# Motorsports_BSPD_EV.net
KiCad netlist of a schematic drawn in Altium Designer
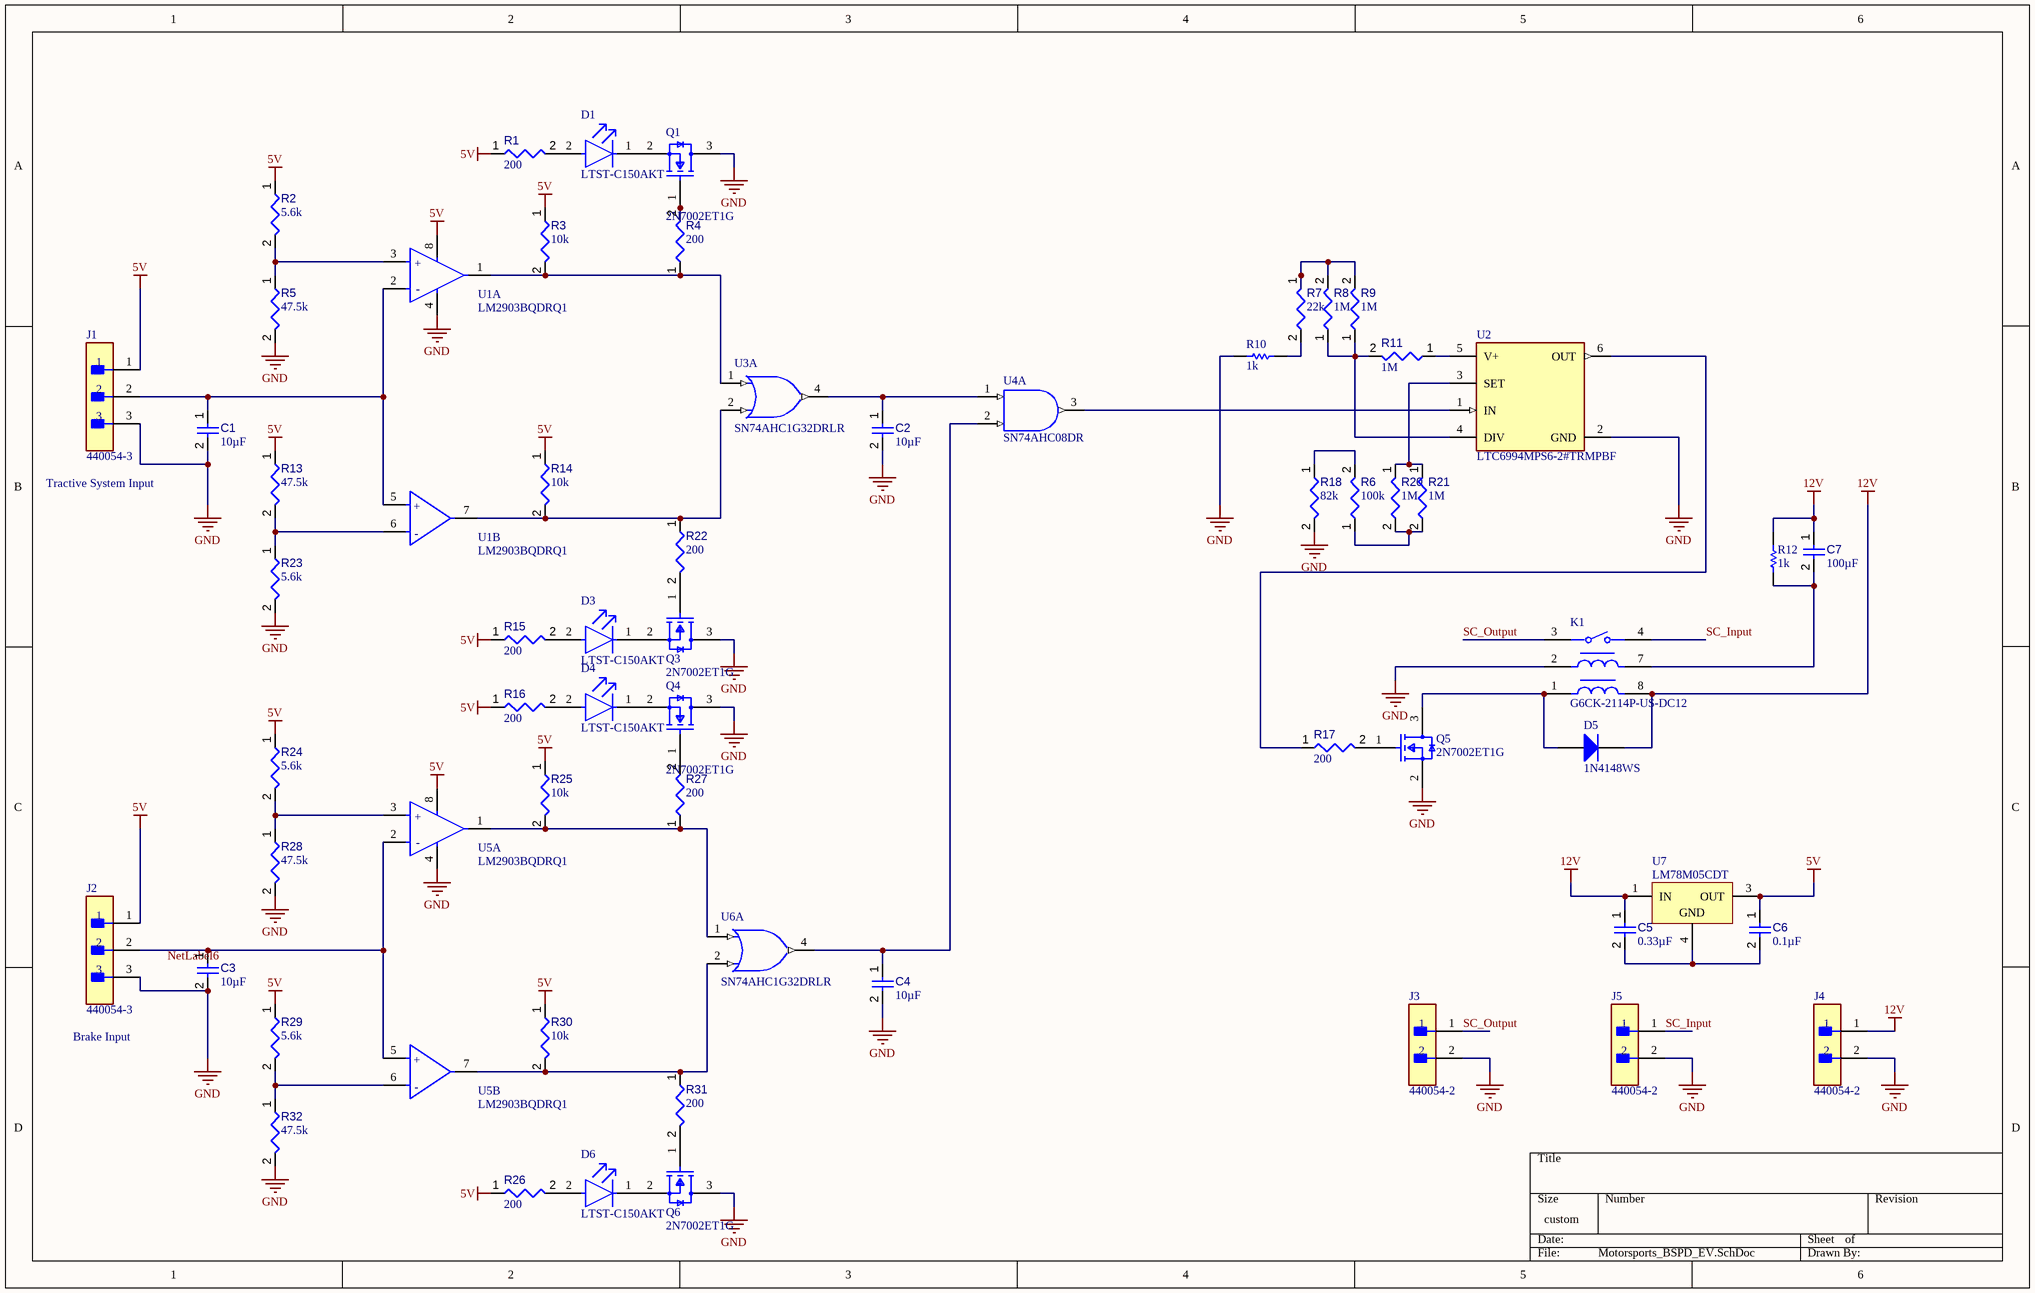
[diagram p0: Motorsports_BSPD_EV.SchDoc]

(export (version "E")
  (design (tool "Eeschema 10.0.6"))
  (components
    (comp (ref "C1")
      (value "10µF")
      (footprint "CAPC0603(1608)100_L")
      (description "Chip Capacitor, 10µF +/-20%, 10V, 0603, Thickness 1 mm")
      (fields (field (name "TOLERANCE") "10%") (field (name "Comment") "Capacitor 10µF +/-20% 10V 0603"))
      (libsource (lib "UGA Motorsports FSAE EV 2026 BSPD") (part "CAP-NP-2"))
    )
    (comp (ref "C2")
      (value "10µF")
      (footprint "CAPC0603(1608)100_L")
      (description "Chip Capacitor, 10µF +/-20%, 10V, 0603, Thickness 1 mm")
      (fields (field (name "TOLERANCE") "10%") (field (name "Comment") "Capacitor 10µF +/-20% 10V 0603"))
      (libsource (lib "UGA Motorsports FSAE EV 2026 BSPD") (part "CAP-NP-2"))
    )
    (comp (ref "C3")
      (value "10µF")
      (footprint "CAPC0603(1608)100_L")
      (description "Chip Capacitor, 10µF +/-20%, 10V, 0603, Thickness 1 mm")
      (fields (field (name "TOLERANCE") "10%") (field (name "Comment") "Capacitor 10µF +/-20% 10V 0603"))
      (libsource (lib "UGA Motorsports FSAE EV 2026 BSPD") (part "CAP-NP-2"))
    )
    (comp (ref "C4")
      (value "10µF")
      (footprint "CAPC0603(1608)100_L")
      (description "Chip Capacitor, 10µF +/-20%, 10V, 0603, Thickness 1 mm")
      (fields (field (name "TOLERANCE") "10%") (field (name "Comment") "Capacitor 10µF +/-20% 10V 0603"))
      (libsource (lib "UGA Motorsports FSAE EV 2026 BSPD") (part "CAP-NP-2"))
    )
    (comp (ref "C5")
      (value "0.33µF")
      (footprint "CAPC0603(1608)100_L")
      (description "Chip Capacitor, 10µF +/-20%, 10V, 0603, Thickness 1 mm")
      (fields (field (name "TOLERANCE") "10%") (field (name "Comment") "Capacitor 10µF +/-20% 10V 0603"))
      (libsource (lib "UGA Motorsports FSAE EV 2026 BSPD") (part "CAP-NP-2"))
    )
    (comp (ref "C6")
      (value "0.1µF")
      (footprint "CAPC0603(1608)100_L")
      (description "Chip Capacitor, 10µF +/-20%, 10V, 0603, Thickness 1 mm")
      (fields (field (name "TOLERANCE") "10%") (field (name "Comment") "Capacitor 10µF +/-20% 10V 0603"))
      (libsource (lib "UGA Motorsports FSAE EV 2026 BSPD") (part "CAP-NP-2"))
    )
    (comp (ref "C7")
      (value "100µF")
      (footprint "CAPC0805(2012)145_L")
      (description "Chip Capacitor, 100µF +/-20%, 6.3V, 0805, Thickness 1.45 mm")
      (fields (field (name "TOLERANCE") "10%") (field (name "Comment") "Capacitor 100µF +/-20% 6.3V 0805"))
      (libsource (lib "UGA Motorsports FSAE EV 2026 BSPD") (part "CAP-NP-2"))
    )
    (comp (ref "D1")
      (value "LTST-C150AKT")
      (footprint "FP-LTST-C150AKT-MFG")
      (description "LED AMBER CLEAR SMD")
      (fields
        (field (name "MANUFACTURER") "Lite-On")
        (field (name "OCTOPART") "https://octopart.com/ltst-c150akt-lite-on-549804")
      )
      (libsource (lib "Altium Content Vault") (part "8706943c75ba83719d021d2fdc84c58"))
    )
    (comp (ref "D3")
      (value "LTST-C150AKT")
      (footprint "FP-LTST-C150AKT-MFG")
      (description "LED AMBER CLEAR SMD")
      (fields
        (field (name "MANUFACTURER") "Lite-On")
        (field (name "OCTOPART") "https://octopart.com/ltst-c150akt-lite-on-549804")
      )
      (libsource (lib "Altium Content Vault") (part "8706943c75ba83719d021d2fdc84c58"))
    )
    (comp (ref "D4")
      (value "LTST-C150AKT")
      (footprint "FP-LTST-C150AKT-MFG")
      (description "LED AMBER CLEAR SMD")
      (fields
        (field (name "MANUFACTURER") "Lite-On")
        (field (name "OCTOPART") "https://octopart.com/ltst-c150akt-lite-on-549804")
      )
      (libsource (lib "Altium Content Vault") (part "8706943c75ba83719d021d2fdc84c58"))
    )
    (comp (ref "D5")
      (value "1N4148WS")
      (footprint "FAIR-SOD-323_V")
      (description "Small Signal Diode, 75 V, 0.15 A, -55 to 150 degC, 2-Pin SOD-323, RoHS, Tape and Reel")
      (fields (field (name "MANUFACTURER") "Fairchild"))
      (libsource (lib "UGA Motorsports FSAE EV 2026 BSPD") (part "D-AK-2"))
    )
    (comp (ref "D6")
      (value "LTST-C150AKT")
      (footprint "FP-LTST-C150AKT-MFG")
      (description "LED AMBER CLEAR SMD")
      (fields
        (field (name "MANUFACTURER") "Lite-On")
        (field (name "OCTOPART") "https://octopart.com/ltst-c150akt-lite-on-549804")
      )
      (libsource (lib "Altium Content Vault") (part "8706943c75ba83719d021d2fdc84c58"))
    )
    (comp (ref "J1")
      (value "440054-3")
      (footprint "FP-440054-3-MFG")
      (description "CONN HEADER VERT 3POS 2MM")
      (fields
        (field (name "OCTOPART") "https://octopart.com/440054-3-te+connectivity-40394845")
        (field (name "MANUFACTURER") "TE Connectivity")
      )
      (libsource (lib "Altium Content Vault") (part "0d3f023dd272f625e17a2be33dea85f"))
    )
    (comp (ref "J2")
      (value "440054-3")
      (footprint "FP-440054-3-MFG")
      (description "CONN HEADER VERT 3POS 2MM")
      (fields
        (field (name "OCTOPART") "https://octopart.com/440054-3-te+connectivity-40394845")
        (field (name "MANUFACTURER") "TE Connectivity")
      )
      (libsource (lib "Altium Content Vault") (part "0d3f023dd272f625e17a2be33dea85f"))
    )
    (comp (ref "J3")
      (value "440054-2")
      (footprint "FP-440054-2-MFG")
      (description "CONN HEADER VERT 2POS 2MM")
      (fields
        (field (name "MANUFACTURER") "TE Connectivity")
        (field (name "OCTOPART") "https://octopart.com/440054-2-te+connectivity-40237927")
      )
      (libsource (lib "Altium Content Vault") (part "3bc925449376181038e59eaffc5286c"))
    )
    (comp (ref "J4")
      (value "440054-2")
      (footprint "FP-440054-2-MFG")
      (description "CONN HEADER VERT 2POS 2MM")
      (fields
        (field (name "MANUFACTURER") "TE Connectivity")
        (field (name "OCTOPART") "https://octopart.com/440054-2-te+connectivity-40237927")
      )
      (libsource (lib "Altium Content Vault") (part "3bc925449376181038e59eaffc5286c"))
    )
    (comp (ref "J5")
      (value "440054-2")
      (footprint "FP-440054-2-MFG")
      (description "CONN HEADER VERT 2POS 2MM")
      (fields
        (field (name "MANUFACTURER") "TE Connectivity")
        (field (name "OCTOPART") "https://octopart.com/440054-2-te+connectivity-40237927")
      )
      (libsource (lib "Altium Content Vault") (part "3bc925449376181038e59eaffc5286c"))
    )
    (comp (ref "K1")
      (value "G6CK-2114P-US-DC12")
      (footprint "FP-G6CK-2114P-US-DC12-MFG")
      (description "RELAY GEN PURPOSE DPST 8A 12V")
      (libsource (lib "Altium Content Vault") (part "248ae269d6825124cdad10c271eae38"))
    )
    (comp (ref "Q1")
      (value "2N7002ET1G")
      (footprint "FP-318-08-IPC_A")
      (description "MOSFET N-CH 60V 260MA SOT-23")
      (libsource (lib "Altium Content Vault") (part "a04dfd38ebfed9f67ad7f4c51a87371"))
    )
    (comp (ref "Q3")
      (value "2N7002ET1G")
      (footprint "FP-318-08-IPC_A")
      (description "MOSFET N-CH 60V 260MA SOT-23")
      (libsource (lib "Altium Content Vault") (part "a04dfd38ebfed9f67ad7f4c51a87371"))
    )
    (comp (ref "Q4")
      (value "2N7002ET1G")
      (footprint "FP-318-08-IPC_A")
      (description "MOSFET N-CH 60V 260MA SOT-23")
      (libsource (lib "Altium Content Vault") (part "a04dfd38ebfed9f67ad7f4c51a87371"))
    )
    (comp (ref "Q5")
      (value "2N7002ET1G")
      (footprint "FP-318-08-IPC_A")
      (description "MOSFET N-CH 60V 260MA SOT-23")
      (libsource (lib "Altium Content Vault") (part "a04dfd38ebfed9f67ad7f4c51a87371"))
    )
    (comp (ref "Q6")
      (value "2N7002ET1G")
      (footprint "FP-318-08-IPC_A")
      (description "MOSFET N-CH 60V 260MA SOT-23")
      (libsource (lib "Altium Content Vault") (part "a04dfd38ebfed9f67ad7f4c51a87371"))
    )
    (comp (ref "R1")
      (value "200")
      (footprint "RESC0402(1005)_L")
      (description "Chip Resistor, 200 Ohms, +/-5 %, 63 mW, -55 to 155 degC, 0402")
      (fields (field (name "POWER") "63mW") (field (name "TOLERANCE") "5%"))
      (libsource (lib "UGA Motorsports FSAE EV 2026 BSPD") (part "RES-2"))
    )
    (comp (ref "R2")
      (value "5.6k")
      (footprint "RESC0402(1005)_L")
      (description "Chip Resistor, 5,6 kOhms, +/-5 %, 63 mW, -55 to 155 degC, 0402")
      (fields (field (name "POWER") "63mW") (field (name "TOLERANCE") "5%"))
      (libsource (lib "UGA Motorsports FSAE EV 2026 BSPD") (part "RES-2"))
    )
    (comp (ref "R3")
      (value "10k")
      (footprint "RESC3216X60X45ML15T20")
      (description "Chip Resistor, 10 KOhm, +/- 1%, 0.25 W, -55 to 155 degC, 1206 (3216 Metric)")
      (fields (field (name "TOLERANCE") "1%") (field (name "POWER") "250mW"))
      (libsource (lib "UGA Motorsports FSAE EV 2026 BSPD") (part "RES-2"))
    )
    (comp (ref "R4")
      (value "200")
      (footprint "RESC0402(1005)_L")
      (description "Chip Resistor, 200 Ohms, +/-5 %, 63 mW, -55 to 155 degC, 0402")
      (fields (field (name "POWER") "63mW") (field (name "TOLERANCE") "5%"))
      (libsource (lib "UGA Motorsports FSAE EV 2026 BSPD") (part "RES-2"))
    )
    (comp (ref "R5")
      (value "47.5k")
      (footprint "RESC0402(1005)_L")
      (description "Chip Resistor, 47,5 kOhms, +/-1 %, 63 mW, -55 to 155 degC, 0402")
      (fields (field (name "POWER") "63mW") (field (name "TOLERANCE") "1%"))
      (libsource (lib "UGA Motorsports FSAE EV 2026 BSPD") (part "RES-2"))
    )
    (comp (ref "R6")
      (value "100k")
      (footprint "RESC1005X40X25ML05T05")
      (description "Chip Resistor, 100 KOhm, +/- 1%, 0.1 W, -55 to 155 degC, 0402 (1005 Metric)")
      (fields (field (name "POWER") "100mW") (field (name "TOLERANCE") "1%"))
      (libsource (lib "UGA Motorsports FSAE EV 2026 BSPD") (part "RES-2"))
    )
    (comp (ref "R7")
      (value "22k")
      (footprint "RESC0402(1005)_L")
      (description "Chip Resistor, 22 kOhms, +/-1 %, 63 mW, -55 to 155 degC, 0402")
      (fields (field (name "POWER") "63mW") (field (name "TOLERANCE") "1%"))
      (libsource (lib "UGA Motorsports FSAE EV 2026 BSPD") (part "RES-2"))
    )
    (comp (ref "R8")
      (value "1M")
      (footprint "RESC0402(1005)_L")
      (description "Chip Resistor, 1 MOhms, +/-5 %, 63 mW, -55 to 155 degC, 0402")
      (fields (field (name "POWER") "63mW") (field (name "TOLERANCE") "5%"))
      (libsource (lib "UGA Motorsports FSAE EV 2026 BSPD") (part "RES-2"))
    )
    (comp (ref "R9")
      (value "1M")
      (footprint "RESC0402(1005)_L")
      (description "Chip Resistor, 1 MOhms, +/-5 %, 63 mW, -55 to 155 degC, 0402")
      (fields (field (name "POWER") "63mW") (field (name "TOLERANCE") "5%"))
      (libsource (lib "UGA Motorsports FSAE EV 2026 BSPD") (part "RES-2"))
    )
    (comp (ref "R10")
      (value "1k")
      (footprint "RESC1005X40X25ML05T05")
      (description "Chip Resistor, 1 KOhm, +/- 1%, 0.1 W, -55 to 155 degC, 0402 (1005 Metric)")
      (fields (field (name "POWER") "100mW") (field (name "TOLERANCE") "1%"))
      (libsource (lib "") (part "RES-2_1"))
    )
    (comp (ref "R11")
      (value "1M")
      (footprint "RESC0402(1005)_L")
      (description "Chip Resistor, 1 MOhms, +/-5 %, 63 mW, -55 to 155 degC, 0402")
      (fields (field (name "POWER") "63mW") (field (name "TOLERANCE") "5%"))
      (libsource (lib "UGA Motorsports FSAE EV 2026 BSPD") (part "RES-2"))
    )
    (comp (ref "R12")
      (value "1k")
      (footprint "RESC1005X40X25ML05T05")
      (description "Chip Resistor, 1 KOhm, +/- 1%, 0.1 W, -55 to 155 degC, 0402 (1005 Metric)")
      (fields (field (name "POWER") "100mW") (field (name "TOLERANCE") "1%"))
      (libsource (lib "") (part "RES-2_1"))
    )
    (comp (ref "R13")
      (value "47.5k")
      (footprint "RESC0402(1005)_L")
      (description "Chip Resistor, 47,5 kOhms, +/-1 %, 63 mW, -55 to 155 degC, 0402")
      (fields (field (name "POWER") "63mW") (field (name "TOLERANCE") "1%"))
      (libsource (lib "UGA Motorsports FSAE EV 2026 BSPD") (part "RES-2"))
    )
    (comp (ref "R14")
      (value "10k")
      (footprint "RESC3216X60X45ML15T20")
      (description "Chip Resistor, 10 KOhm, +/- 1%, 0.25 W, -55 to 155 degC, 1206 (3216 Metric)")
      (fields (field (name "TOLERANCE") "1%") (field (name "POWER") "250mW"))
      (libsource (lib "UGA Motorsports FSAE EV 2026 BSPD") (part "RES-2"))
    )
    (comp (ref "R15")
      (value "200")
      (footprint "RESC0402(1005)_L")
      (description "Chip Resistor, 200 Ohms, +/-5 %, 63 mW, -55 to 155 degC, 0402")
      (fields (field (name "POWER") "63mW") (field (name "TOLERANCE") "5%"))
      (libsource (lib "UGA Motorsports FSAE EV 2026 BSPD") (part "RES-2"))
    )
    (comp (ref "R16")
      (value "200")
      (footprint "RESC0402(1005)_L")
      (description "Chip Resistor, 200 Ohms, +/-5 %, 63 mW, -55 to 155 degC, 0402")
      (fields (field (name "POWER") "63mW") (field (name "TOLERANCE") "5%"))
      (libsource (lib "UGA Motorsports FSAE EV 2026 BSPD") (part "RES-2"))
    )
    (comp (ref "R17")
      (value "200")
      (footprint "RESC0402(1005)_L")
      (description "Chip Resistor, 200 Ohms, +/-5 %, 63 mW, -55 to 155 degC, 0402")
      (fields (field (name "POWER") "63mW") (field (name "TOLERANCE") "5%"))
      (libsource (lib "UGA Motorsports FSAE EV 2026 BSPD") (part "RES-2"))
    )
    (comp (ref "R18")
      (value "82k")
      (footprint "RESC0402(1005)_L")
      (description "Chip Resistor, 82 kOhms, +/-1 %, 63 mW, -55 to 155 degC, 0402")
      (fields (field (name "POWER") "63mW") (field (name "TOLERANCE") "1%"))
      (libsource (lib "UGA Motorsports FSAE EV 2026 BSPD") (part "RES-2"))
    )
    (comp (ref "R20")
      (value "1M")
      (footprint "RESC0402(1005)_L")
      (description "Chip Resistor, 1 MOhms, +/-5 %, 63 mW, -55 to 155 degC, 0402")
      (fields (field (name "POWER") "63mW") (field (name "TOLERANCE") "5%"))
      (libsource (lib "UGA Motorsports FSAE EV 2026 BSPD") (part "RES-2"))
    )
    (comp (ref "R21")
      (value "1M")
      (footprint "RESC0402(1005)_L")
      (description "Chip Resistor, 1 MOhms, +/-5 %, 63 mW, -55 to 155 degC, 0402")
      (fields (field (name "POWER") "63mW") (field (name "TOLERANCE") "5%"))
      (libsource (lib "UGA Motorsports FSAE EV 2026 BSPD") (part "RES-2"))
    )
    (comp (ref "R22")
      (value "200")
      (footprint "RESC0402(1005)_L")
      (description "Chip Resistor, 200 Ohms, +/-5 %, 63 mW, -55 to 155 degC, 0402")
      (fields (field (name "POWER") "63mW") (field (name "TOLERANCE") "5%"))
      (libsource (lib "UGA Motorsports FSAE EV 2026 BSPD") (part "RES-2"))
    )
    (comp (ref "R23")
      (value "5.6k")
      (footprint "RESC0402(1005)_L")
      (description "Chip Resistor, 5,6 kOhms, +/-5 %, 63 mW, -55 to 155 degC, 0402")
      (fields (field (name "POWER") "63mW") (field (name "TOLERANCE") "5%"))
      (libsource (lib "UGA Motorsports FSAE EV 2026 BSPD") (part "RES-2"))
    )
    (comp (ref "R24")
      (value "5.6k")
      (footprint "RESC0402(1005)_L")
      (description "Chip Resistor, 5,6 kOhms, +/-5 %, 63 mW, -55 to 155 degC, 0402")
      (fields (field (name "POWER") "63mW") (field (name "TOLERANCE") "5%"))
      (libsource (lib "UGA Motorsports FSAE EV 2026 BSPD") (part "RES-2"))
    )
    (comp (ref "R25")
      (value "10k")
      (footprint "RESC3216X60X45ML15T20")
      (description "Chip Resistor, 10 KOhm, +/- 1%, 0.25 W, -55 to 155 degC, 1206 (3216 Metric)")
      (fields (field (name "TOLERANCE") "1%") (field (name "POWER") "250mW"))
      (libsource (lib "UGA Motorsports FSAE EV 2026 BSPD") (part "RES-2"))
    )
    (comp (ref "R26")
      (value "200")
      (footprint "RESC0402(1005)_L")
      (description "Chip Resistor, 200 Ohms, +/-5 %, 63 mW, -55 to 155 degC, 0402")
      (fields (field (name "POWER") "63mW") (field (name "TOLERANCE") "5%"))
      (libsource (lib "UGA Motorsports FSAE EV 2026 BSPD") (part "RES-2"))
    )
    (comp (ref "R27")
      (value "200")
      (footprint "RESC0402(1005)_L")
      (description "Chip Resistor, 200 Ohms, +/-5 %, 63 mW, -55 to 155 degC, 0402")
      (fields (field (name "POWER") "63mW") (field (name "TOLERANCE") "5%"))
      (libsource (lib "UGA Motorsports FSAE EV 2026 BSPD") (part "RES-2"))
    )
    (comp (ref "R28")
      (value "47.5k")
      (footprint "RESC0402(1005)_L")
      (description "Chip Resistor, 47,5 kOhms, +/-1 %, 63 mW, -55 to 155 degC, 0402")
      (fields (field (name "POWER") "63mW") (field (name "TOLERANCE") "1%"))
      (libsource (lib "UGA Motorsports FSAE EV 2026 BSPD") (part "RES-2"))
    )
    (comp (ref "R29")
      (value "5.6k")
      (footprint "RESC0402(1005)_L")
      (description "Chip Resistor, 5,6 kOhms, +/-5 %, 63 mW, -55 to 155 degC, 0402")
      (fields (field (name "POWER") "63mW") (field (name "TOLERANCE") "5%"))
      (libsource (lib "UGA Motorsports FSAE EV 2026 BSPD") (part "RES-2"))
    )
    (comp (ref "R30")
      (value "10k")
      (footprint "RESC3216X60X45ML15T20")
      (description "Chip Resistor, 10 KOhm, +/- 1%, 0.25 W, -55 to 155 degC, 1206 (3216 Metric)")
      (fields (field (name "TOLERANCE") "1%") (field (name "POWER") "250mW"))
      (libsource (lib "UGA Motorsports FSAE EV 2026 BSPD") (part "RES-2"))
    )
    (comp (ref "R31")
      (value "200")
      (footprint "RESC0402(1005)_L")
      (description "Chip Resistor, 200 Ohms, +/-5 %, 63 mW, -55 to 155 degC, 0402")
      (fields (field (name "POWER") "63mW") (field (name "TOLERANCE") "5%"))
      (libsource (lib "UGA Motorsports FSAE EV 2026 BSPD") (part "RES-2"))
    )
    (comp (ref "R32")
      (value "47.5k")
      (footprint "RESC0402(1005)_L")
      (description "Chip Resistor, 47,5 kOhms, +/-1 %, 63 mW, -55 to 155 degC, 0402")
      (fields (field (name "POWER") "63mW") (field (name "TOLERANCE") "1%"))
      (libsource (lib "UGA Motorsports FSAE EV 2026 BSPD") (part "RES-2"))
    )
    (comp (ref "U1")
      (value "LM2903BQDRQ1")
      (footprint "FP-D0008A-MFG")
      (description "Automotive Dual Comparators")
      (fields
        (field (name "MANUFACTURER") "Texas Instruments")
        (field (name "OCTOPART") "https://octopart.com/lm2903bqdrq1-texas+instruments-107383907")
      )
      (libsource (lib "Altium Content Vault") (part "d0dfe35d032f86ae96c0c3919f86c94"))
    )
    (comp (ref "U2")
      (value "LTC6994MPS6-2#TRMPBF")
      (footprint "FP-S6-6-05-08-1636-MFG")
      (description "IC DELAY LINE 8TAP PROG TSOT23-6")
      (libsource (lib "Altium Content Vault") (part "5813ba12ddd9e7c0a16514c8272ed63"))
    )
    (comp (ref "U3")
      (value "SN74AHC1G32DRLR")
      (footprint "DRL0005A_N")
      (description "Single 2-Input Positive-OR Gate, DRL0005A, LARGE T&R")
      (fields
        (field (name "GENERIC PART NUMBER") "SN74AHC1G32")
        (field (name "MANUFACTURER") "Texas Instruments")
      )
      (libsource (lib "Altium Content Vault") (part "TI-SN74XXX1X32-5"))
    )
    (comp (ref "U4")
      (value "SN74AHC08DR")
      (footprint "D0014A_L")
      (description "Quadruple 2-Input Positive-AND Gates, D0014A, LARGE T&R")
      (fields
        (field (name "GENERIC PART NUMBER") "SN74AHC08")
        (field (name "MANUFACTURER") "Texas Instruments")
      )
      (libsource (lib "Altium Content Vault") (part "TI-AND-4-2IN-14"))
    )
    (comp (ref "U5")
      (value "LM2903BQDRQ1")
      (footprint "FP-D0008A-MFG")
      (description "Automotive Dual Comparators")
      (fields
        (field (name "MANUFACTURER") "Texas Instruments")
        (field (name "OCTOPART") "https://octopart.com/lm2903bqdrq1-texas+instruments-107383907")
      )
      (libsource (lib "Altium Content Vault") (part "d0dfe35d032f86ae96c0c3919f86c94"))
    )
    (comp (ref "U6")
      (value "SN74AHC1G32DRLR")
      (footprint "DRL0005A_N")
      (description "Single 2-Input Positive-OR Gate, DRL0005A, LARGE T&R")
      (fields
        (field (name "GENERIC PART NUMBER") "SN74AHC1G32")
        (field (name "MANUFACTURER") "Texas Instruments")
      )
      (libsource (lib "Altium Content Vault") (part "TI-SN74XXX1X32-5"))
    )
    (comp (ref "U7")
      (value "LM78M05CDT")
      (footprint "NDP0003B_N")
      (description "3-Terminal Positive Voltage Regulators, 3-pin TO-252")
      (fields (field (name "MANUFACTURER") "Texas Instruments"))
      (libsource (lib "Altium Content Vault") (part "PM-REG-LM78M05-SOT3"))
    )
  )
  (nets
    (net (code "2") (name "/SC_Input") (class "Default")
      (node (ref "J5") (pin "1") (pinfunction "1_1") (pintype "passive"))
      (node (ref "K1") (pin "4") (pinfunction "4_4") (pintype "passive"))
    )
    (net (code "3") (name "/SC_Output") (class "Default")
      (node (ref "J3") (pin "1") (pinfunction "1_1") (pintype "passive"))
      (node (ref "K1") (pin "3") (pinfunction "3_3") (pintype "passive"))
    )
    (net (code "4") (name "5V") (class "Default")
      (node (ref "C6") (pin "1") (pinfunction "1_1") (pintype "passive"))
      (node (ref "J1") (pin "1") (pinfunction "1_1") (pintype "passive"))
      (node (ref "J2") (pin "1") (pinfunction "1_1") (pintype "passive"))
      (node (ref "R1") (pin "1") (pinfunction "1_1") (pintype "passive"))
      (node (ref "R13") (pin "1") (pinfunction "1_1") (pintype "passive"))
      (node (ref "R14") (pin "1") (pinfunction "1_1") (pintype "passive"))
      (node (ref "R15") (pin "1") (pinfunction "1_1") (pintype "passive"))
      (node (ref "R16") (pin "1") (pinfunction "1_1") (pintype "passive"))
      (node (ref "R2") (pin "1") (pinfunction "1_1") (pintype "passive"))
      (node (ref "R24") (pin "1") (pinfunction "1_1") (pintype "passive"))
      (node (ref "R25") (pin "1") (pinfunction "1_1") (pintype "passive"))
      (node (ref "R26") (pin "1") (pinfunction "1_1") (pintype "passive"))
      (node (ref "R29") (pin "1") (pinfunction "1_1") (pintype "passive"))
      (node (ref "R3") (pin "1") (pinfunction "1_1") (pintype "passive"))
      (node (ref "R30") (pin "1") (pinfunction "1_1") (pintype "passive"))
      (node (ref "U1") (pin "8") (pinfunction "VCC_8") (pintype "power_in"))
      (node (ref "U5") (pin "8") (pinfunction "VCC_8") (pintype "power_in"))
      (node (ref "U7") (pin "3") (pinfunction "OUT_3") (pintype "power_in"))
    )
    (net (code "5") (name "12V") (class "Default")
      (node (ref "C5") (pin "1") (pinfunction "1_1") (pintype "passive"))
      (node (ref "C7") (pin "1") (pinfunction "1_1") (pintype "passive"))
      (node (ref "D5") (pin "2") (pinfunction "K_2") (pintype "passive"))
      (node (ref "J4") (pin "1") (pinfunction "1_1") (pintype "passive"))
      (node (ref "K1") (pin "8") (pinfunction "S+_8") (pintype "passive"))
      (node (ref "R12") (pin "2") (pinfunction "2_2") (pintype "passive"))
      (node (ref "U7") (pin "1") (pinfunction "IN_1") (pintype "power_in"))
    )
    (net (code "6") (name "GND") (class "Default")
      (node (ref "C1") (pin "2") (pinfunction "2_2") (pintype "passive"))
      (node (ref "C2") (pin "2") (pinfunction "2_2") (pintype "passive"))
      (node (ref "C3") (pin "2") (pinfunction "2_2") (pintype "passive"))
      (node (ref "C4") (pin "2") (pinfunction "2_2") (pintype "passive"))
      (node (ref "J1") (pin "3") (pinfunction "3_3") (pintype "passive"))
      (node (ref "J2") (pin "3") (pinfunction "3_3") (pintype "passive"))
      (node (ref "J3") (pin "2") (pinfunction "2_2") (pintype "passive"))
      (node (ref "J4") (pin "2") (pinfunction "2_2") (pintype "passive"))
      (node (ref "J5") (pin "2") (pinfunction "2_2") (pintype "passive"))
      (node (ref "K1") (pin "2") (pinfunction "R-_2") (pintype "passive"))
      (node (ref "Q1") (pin "3") (pinfunction "Drain_3") (pintype "passive"))
      (node (ref "Q3") (pin "3") (pinfunction "Drain_3") (pintype "passive"))
      (node (ref "Q4") (pin "3") (pinfunction "Drain_3") (pintype "passive"))
      (node (ref "Q5") (pin "2") (pinfunction "Source_2") (pintype "passive"))
      (node (ref "Q6") (pin "3") (pinfunction "Drain_3") (pintype "passive"))
      (node (ref "R10") (pin "2") (pinfunction "2_2") (pintype "passive"))
      (node (ref "R18") (pin "2") (pinfunction "2_2") (pintype "passive"))
      (node (ref "R23") (pin "2") (pinfunction "2_2") (pintype "passive"))
      (node (ref "R28") (pin "2") (pinfunction "2_2") (pintype "passive"))
      (node (ref "R32") (pin "2") (pinfunction "2_2") (pintype "passive"))
      (node (ref "R5") (pin "2") (pinfunction "2_2") (pintype "passive"))
      (node (ref "U1") (pin "4") (pinfunction "GND_4") (pintype "power_in"))
      (node (ref "U2") (pin "2") (pinfunction "GND_2") (pintype "power_in"))
      (node (ref "U5") (pin "4") (pinfunction "GND_4") (pintype "power_in"))
    )
    (net (code "7") (name "Net-(D1-A)") (class "Default")
      (node (ref "D1") (pin "2") (pinfunction "A_2") (pintype "passive"))
      (node (ref "R1") (pin "2") (pinfunction "2_2") (pintype "passive"))
    )
    (net (code "8") (name "Net-(D1-C)") (class "Default")
      (node (ref "D1") (pin "1") (pinfunction "C_1") (pintype "passive"))
      (node (ref "Q1") (pin "2") (pinfunction "Source_2") (pintype "passive"))
    )
    (net (code "9") (name "Net-(D3-A)") (class "Default")
      (node (ref "D3") (pin "2") (pinfunction "A_2") (pintype "passive"))
      (node (ref "R15") (pin "2") (pinfunction "2_2") (pintype "passive"))
    )
    (net (code "10") (name "Net-(D3-C)") (class "Default")
      (node (ref "D3") (pin "1") (pinfunction "C_1") (pintype "passive"))
      (node (ref "Q3") (pin "2") (pinfunction "Source_2") (pintype "passive"))
    )
    (net (code "11") (name "Net-(D4-A)") (class "Default")
      (node (ref "D4") (pin "2") (pinfunction "A_2") (pintype "passive"))
      (node (ref "R16") (pin "2") (pinfunction "2_2") (pintype "passive"))
    )
    (net (code "12") (name "Net-(D4-C)") (class "Default")
      (node (ref "D4") (pin "1") (pinfunction "C_1") (pintype "passive"))
      (node (ref "Q4") (pin "2") (pinfunction "Source_2") (pintype "passive"))
    )
    (net (code "13") (name "Net-(D5-A)") (class "Default")
      (node (ref "D5") (pin "1") (pinfunction "A_1") (pintype "passive"))
      (node (ref "K1") (pin "1") (pinfunction "S-_1") (pintype "passive"))
      (node (ref "Q5") (pin "3") (pinfunction "Drain_3") (pintype "passive"))
    )
    (net (code "14") (name "Net-(D6-A)") (class "Default")
      (node (ref "D6") (pin "2") (pinfunction "A_2") (pintype "passive"))
      (node (ref "R26") (pin "2") (pinfunction "2_2") (pintype "passive"))
    )
    (net (code "15") (name "Net-(D6-C)") (class "Default")
      (node (ref "D6") (pin "1") (pinfunction "C_1") (pintype "passive"))
      (node (ref "Q6") (pin "2") (pinfunction "Source_2") (pintype "passive"))
    )
    (net (code "16") (name "Net-(K1-R+)") (class "Default")
      (node (ref "C7") (pin "2") (pinfunction "2_2") (pintype "passive"))
      (node (ref "K1") (pin "7") (pinfunction "R+_7") (pintype "passive"))
      (node (ref "R12") (pin "1") (pinfunction "1_1") (pintype "passive"))
    )
    (net (code "17") (name "Net-(Q1-Gate)") (class "Default")
      (node (ref "Q1") (pin "1") (pinfunction "Gate_1") (pintype "passive"))
      (node (ref "R4") (pin "2") (pinfunction "2_2") (pintype "passive"))
    )
    (net (code "18") (name "Net-(Q3-Gate)") (class "Default")
      (node (ref "Q3") (pin "1") (pinfunction "Gate_1") (pintype "passive"))
      (node (ref "R22") (pin "2") (pinfunction "2_2") (pintype "passive"))
    )
    (net (code "19") (name "Net-(Q4-Gate)") (class "Default")
      (node (ref "Q4") (pin "1") (pinfunction "Gate_1") (pintype "passive"))
      (node (ref "R27") (pin "2") (pinfunction "2_2") (pintype "passive"))
    )
    (net (code "20") (name "Net-(Q5-Gate)") (class "Default")
      (node (ref "Q5") (pin "1") (pinfunction "Gate_1") (pintype "passive"))
      (node (ref "R17") (pin "2") (pinfunction "2_2") (pintype "passive"))
    )
    (net (code "21") (name "Net-(Q6-Gate)") (class "Default")
      (node (ref "Q6") (pin "1") (pinfunction "Gate_1") (pintype "passive"))
      (node (ref "R31") (pin "2") (pinfunction "2_2") (pintype "passive"))
    )
    (net (code "22") (name "Net-(R7-Pad1)") (class "Default")
      (node (ref "R7") (pin "1") (pinfunction "1_1") (pintype "passive"))
      (node (ref "R8") (pin "2") (pinfunction "2_2") (pintype "passive"))
      (node (ref "R9") (pin "2") (pinfunction "2_2") (pintype "passive"))
    )
    (net (code "23") (name "Net-(R10-Pad1)") (class "Default")
      (node (ref "R10") (pin "1") (pinfunction "1_1") (pintype "passive"))
      (node (ref "R7") (pin "2") (pinfunction "2_2") (pintype "passive"))
    )
    (net (code "24") (name "Net-(R18-Pad1)") (class "Default")
      (node (ref "R18") (pin "1") (pinfunction "1_1") (pintype "passive"))
      (node (ref "R6") (pin "2") (pinfunction "2_2") (pintype "passive"))
    )
    (net (code "25") (name "Net-(R20-Pad2)") (class "Default")
      (node (ref "R20") (pin "2") (pinfunction "2_2") (pintype "passive"))
      (node (ref "R21") (pin "2") (pinfunction "2_2") (pintype "passive"))
      (node (ref "R6") (pin "1") (pinfunction "1_1") (pintype "passive"))
    )
    (net (code "26") (name "Net-(U1A-1IN+)") (class "Default")
      (node (ref "R2") (pin "2") (pinfunction "2_2") (pintype "passive"))
      (node (ref "R5") (pin "1") (pinfunction "1_1") (pintype "passive"))
      (node (ref "U1") (pin "3") (pinfunction "1IN+_3") (pintype "tri_state"))
    )
    (net (code "27") (name "Net-(U1A-1IN-)") (class "Default")
      (node (ref "C1") (pin "1") (pinfunction "1_1") (pintype "passive"))
      (node (ref "J1") (pin "2") (pinfunction "2_2") (pintype "passive"))
      (node (ref "U1") (pin "2") (pinfunction "1IN-_2") (pintype "tri_state"))
      (node (ref "U1") (pin "5") (pinfunction "2IN+_5") (pintype "tri_state"))
    )
    (net (code "28") (name "Net-(U1A-1OUT)") (class "Default")
      (node (ref "R3") (pin "2") (pinfunction "2_2") (pintype "passive"))
      (node (ref "R4") (pin "1") (pinfunction "1_1") (pintype "passive"))
      (node (ref "U1") (pin "1") (pinfunction "1OUT_1") (pintype "passive"))
      (node (ref "U3") (pin "1") (pinfunction "A_1") (pintype "input"))
    )
    (net (code "29") (name "Net-(U1B-2IN-)") (class "Default")
      (node (ref "R13") (pin "2") (pinfunction "2_2") (pintype "passive"))
      (node (ref "R23") (pin "1") (pinfunction "1_1") (pintype "passive"))
      (node (ref "U1") (pin "6") (pinfunction "2IN-_6") (pintype "tri_state"))
    )
    (net (code "30") (name "Net-(U1B-2OUT)") (class "Default")
      (node (ref "R14") (pin "2") (pinfunction "2_2") (pintype "passive"))
      (node (ref "R22") (pin "1") (pinfunction "1_1") (pintype "passive"))
      (node (ref "U1") (pin "7") (pinfunction "2OUT_7") (pintype "passive"))
      (node (ref "U3") (pin "2") (pinfunction "B_2") (pintype "input"))
    )
    (net (code "31") (name "Net-(U2-DIV)") (class "Default")
      (node (ref "R11") (pin "2") (pinfunction "2_2") (pintype "passive"))
      (node (ref "R8") (pin "1") (pinfunction "1_1") (pintype "passive"))
      (node (ref "R9") (pin "1") (pinfunction "1_1") (pintype "passive"))
      (node (ref "U2") (pin "4") (pinfunction "DIV_4") (pintype "passive"))
    )
    (net (code "32") (name "Net-(U2-IN)") (class "Default")
      (node (ref "U2") (pin "1") (pinfunction "IN_1") (pintype "input"))
      (node (ref "U4") (pin "3") (pinfunction "1Y_3") (pintype "output"))
    )
    (net (code "33") (name "Net-(U2-OUT)") (class "Default")
      (node (ref "R17") (pin "1") (pinfunction "1_1") (pintype "passive"))
      (node (ref "U2") (pin "6") (pinfunction "OUT_6") (pintype "output"))
    )
    (net (code "34") (name "Net-(U2-SET)") (class "Default")
      (node (ref "R20") (pin "1") (pinfunction "1_1") (pintype "passive"))
      (node (ref "R21") (pin "1") (pinfunction "1_1") (pintype "passive"))
      (node (ref "U2") (pin "3") (pinfunction "SET_3") (pintype "passive"))
    )
    (net (code "35") (name "Net-(U2-V+)") (class "Default")
      (node (ref "R11") (pin "1") (pinfunction "1_1") (pintype "passive"))
      (node (ref "U2") (pin "5") (pinfunction "V+_5") (pintype "power_in"))
    )
    (net (code "36") (name "Net-(U3A-Y)") (class "Default")
      (node (ref "C2") (pin "1") (pinfunction "1_1") (pintype "passive"))
      (node (ref "U3") (pin "4") (pinfunction "Y_4") (pintype "output"))
      (node (ref "U4") (pin "1") (pinfunction "1A_1") (pintype "input"))
    )
    (net (code "37") (name "Net-(U4A-1B)") (class "Default")
      (node (ref "C4") (pin "1") (pinfunction "1_1") (pintype "passive"))
      (node (ref "U4") (pin "2") (pinfunction "1B_2") (pintype "input"))
      (node (ref "U6") (pin "4") (pinfunction "Y_4") (pintype "output"))
    )
    (net (code "38") (name "Net-(U5A-1IN+)") (class "Default")
      (node (ref "R24") (pin "2") (pinfunction "2_2") (pintype "passive"))
      (node (ref "R28") (pin "1") (pinfunction "1_1") (pintype "passive"))
      (node (ref "U5") (pin "3") (pinfunction "1IN+_3") (pintype "tri_state"))
    )
    (net (code "39") (name "Net-(U5A-1IN-)") (class "Default")
      (node (ref "C3") (pin "1") (pinfunction "1_1") (pintype "passive"))
      (node (ref "J2") (pin "2") (pinfunction "2_2") (pintype "passive"))
      (node (ref "U5") (pin "2") (pinfunction "1IN-_2") (pintype "tri_state"))
      (node (ref "U5") (pin "5") (pinfunction "2IN+_5") (pintype "tri_state"))
    )
    (net (code "40") (name "Net-(U5A-1OUT)") (class "Default")
      (node (ref "R25") (pin "2") (pinfunction "2_2") (pintype "passive"))
      (node (ref "R27") (pin "1") (pinfunction "1_1") (pintype "passive"))
      (node (ref "U5") (pin "1") (pinfunction "1OUT_1") (pintype "passive"))
      (node (ref "U6") (pin "1") (pinfunction "A_1") (pintype "input"))
    )
    (net (code "41") (name "Net-(U5B-2IN-)") (class "Default")
      (node (ref "R29") (pin "2") (pinfunction "2_2") (pintype "passive"))
      (node (ref "R32") (pin "1") (pinfunction "1_1") (pintype "passive"))
      (node (ref "U5") (pin "6") (pinfunction "2IN-_6") (pintype "tri_state"))
    )
    (net (code "42") (name "Net-(U5B-2OUT)") (class "Default")
      (node (ref "R30") (pin "2") (pinfunction "2_2") (pintype "passive"))
      (node (ref "R31") (pin "1") (pinfunction "1_1") (pintype "passive"))
      (node (ref "U5") (pin "7") (pinfunction "2OUT_7") (pintype "passive"))
      (node (ref "U6") (pin "2") (pinfunction "B_2") (pintype "input"))
    )
    (net (code "43") (name "Net-(U7-GND)") (class "Default")
      (node (ref "C5") (pin "2") (pinfunction "2_2") (pintype "passive"))
      (node (ref "C6") (pin "2") (pinfunction "2_2") (pintype "passive"))
      (node (ref "U7") (pin "4") (pinfunction "GND_4") (pintype "power_in"))
    )
  )
)
